# WATCHDOG.net
KiCad netlist of a schematic drawn in Altium Designer
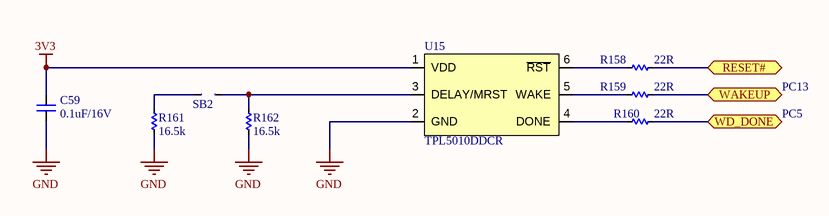
[diagram p0: WATCHDOG.SchDoc]

(export (version "E")
  (design (tool "Eeschema 10.0.6"))
  (components
    (comp (ref "C59")
      (value "0.1uF/16V")
      (footprint "CAP_C_1608X80")
      (description "CAP_Chip")
      (libsource (lib "LABLIB") (part "CAP_SMD"))
    )
    (comp (ref "R158")
      (value "22R")
      (footprint "RES_C_1608X60")
      (description "RES")
      (libsource (lib "LABLIB") (part "_RES_B_2"))
    )
    (comp (ref "R159")
      (value "22R")
      (footprint "RES_C_1608X60")
      (description "RES")
      (libsource (lib "LABLIB") (part "_RES_B_2"))
    )
    (comp (ref "R160")
      (value "22R")
      (footprint "RES_C_1608X60")
      (description "RES")
      (libsource (lib "LABLIB") (part "_RES_B_2"))
    )
    (comp (ref "R161")
      (value "16.5k")
      (footprint "RES_C_1608X60")
      (description "RES")
      (libsource (lib "LABLIB") (part "_RES_B_2"))
    )
    (comp (ref "R162")
      (value "16.5k")
      (footprint "RES_C_1608X60")
      (description "RES")
      (libsource (lib "LABLIB") (part "_RES_B_2"))
    )
    (comp (ref "SB2")
      (value "JUMPER")
      (footprint "JUMPER_1608")
      (libsource (lib "COMM_SCHLIB") (part "JUMPER"))
    )
    (comp (ref "U15")
      (value "TPL5010DDCR")
      (footprint "TPL5010DDCR")
      (description "OSC PROG TIMER TSOT23-6")
      (libsource (lib "COMM_SCHLIB") (part "TPL5010DDCR"))
    )
  )
  (nets
    (net (code "1") (name "/RESET#") (class "Default")
      (node (ref "R158") (pin "2") (pinfunction "2_2") (pintype "passive"))
    )
    (net (code "2") (name "/WAKEUP") (class "Default")
      (node (ref "R159") (pin "2") (pinfunction "2_2") (pintype "passive"))
    )
    (net (code "3") (name "/WD_DONE") (class "Default")
      (node (ref "R160") (pin "2") (pinfunction "2_2") (pintype "passive"))
    )
    (net (code "4") (name "3V3") (class "Default")
      (node (ref "C59") (pin "2") (pinfunction "2_2") (pintype "passive"))
      (node (ref "U15") (pin "1") (pinfunction "VDD_1") (pintype "passive"))
    )
    (net (code "5") (name "GND") (class "Default")
      (node (ref "C59") (pin "1") (pinfunction "1_1") (pintype "passive"))
      (node (ref "R161") (pin "1") (pinfunction "1_1") (pintype "passive"))
      (node (ref "R162") (pin "1") (pinfunction "1_1") (pintype "passive"))
      (node (ref "U15") (pin "2") (pinfunction "GND_2") (pintype "passive"))
    )
    (net (code "6") (name "Net-(R161-Pad2)") (class "Default")
      (node (ref "R161") (pin "2") (pinfunction "2_2") (pintype "passive"))
      (node (ref "SB2") (pin "1") (pinfunction "1_1") (pintype "passive"))
    )
    (net (code "7") (name "Net-(U15-DELAY{slash}MRST)") (class "Default")
      (node (ref "R162") (pin "2") (pinfunction "2_2") (pintype "passive"))
      (node (ref "SB2") (pin "2") (pinfunction "2_2") (pintype "passive"))
      (node (ref "U15") (pin "3") (pinfunction "DELAY/MRST_3") (pintype "passive"))
    )
    (net (code "8") (name "Net-(U15-DONE)") (class "Default")
      (node (ref "R160") (pin "1") (pinfunction "1_1") (pintype "passive"))
      (node (ref "U15") (pin "4") (pinfunction "DONE_4") (pintype "passive"))
    )
    (net (code "9") (name "Net-(U15-WAKE)") (class "Default")
      (node (ref "R159") (pin "1") (pinfunction "1_1") (pintype "passive"))
      (node (ref "U15") (pin "5") (pinfunction "WAKE_5") (pintype "passive"))
    )
    (net (code "10") (name "Net-(U15-~{RST})") (class "Default")
      (node (ref "R158") (pin "1") (pinfunction "1_1") (pintype "passive"))
      (node (ref "U15") (pin "6") (pinfunction "~{RST}_6") (pintype "passive"))
    )
  )
)
